# TSOC_CYBLE_R0_0.net
KiCad netlist of a schematic drawn in EAGLE
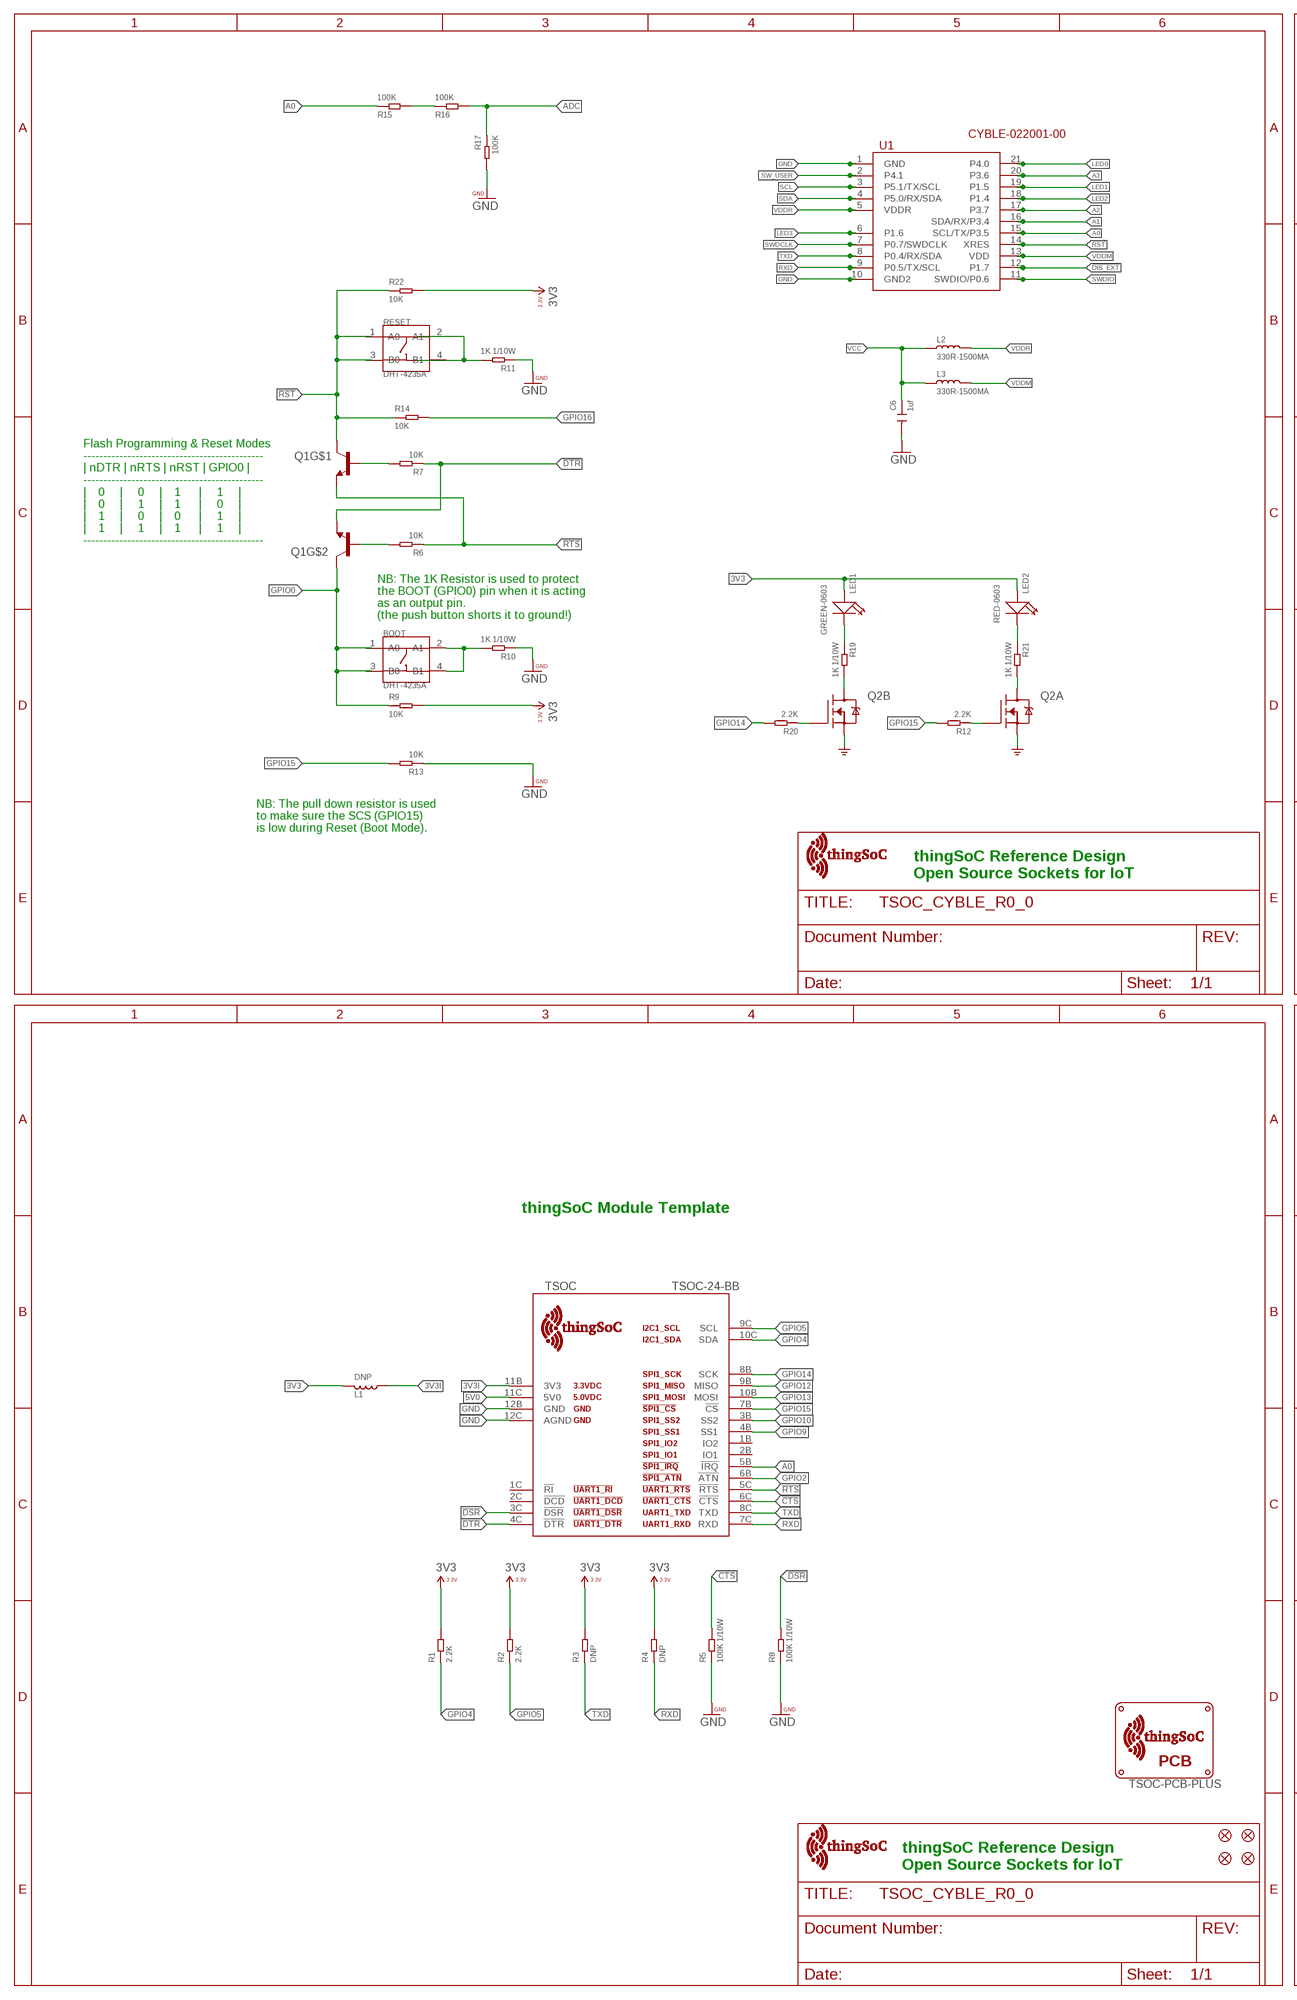
[diagram p0: schematic, sheet 1, part 1 of 2]
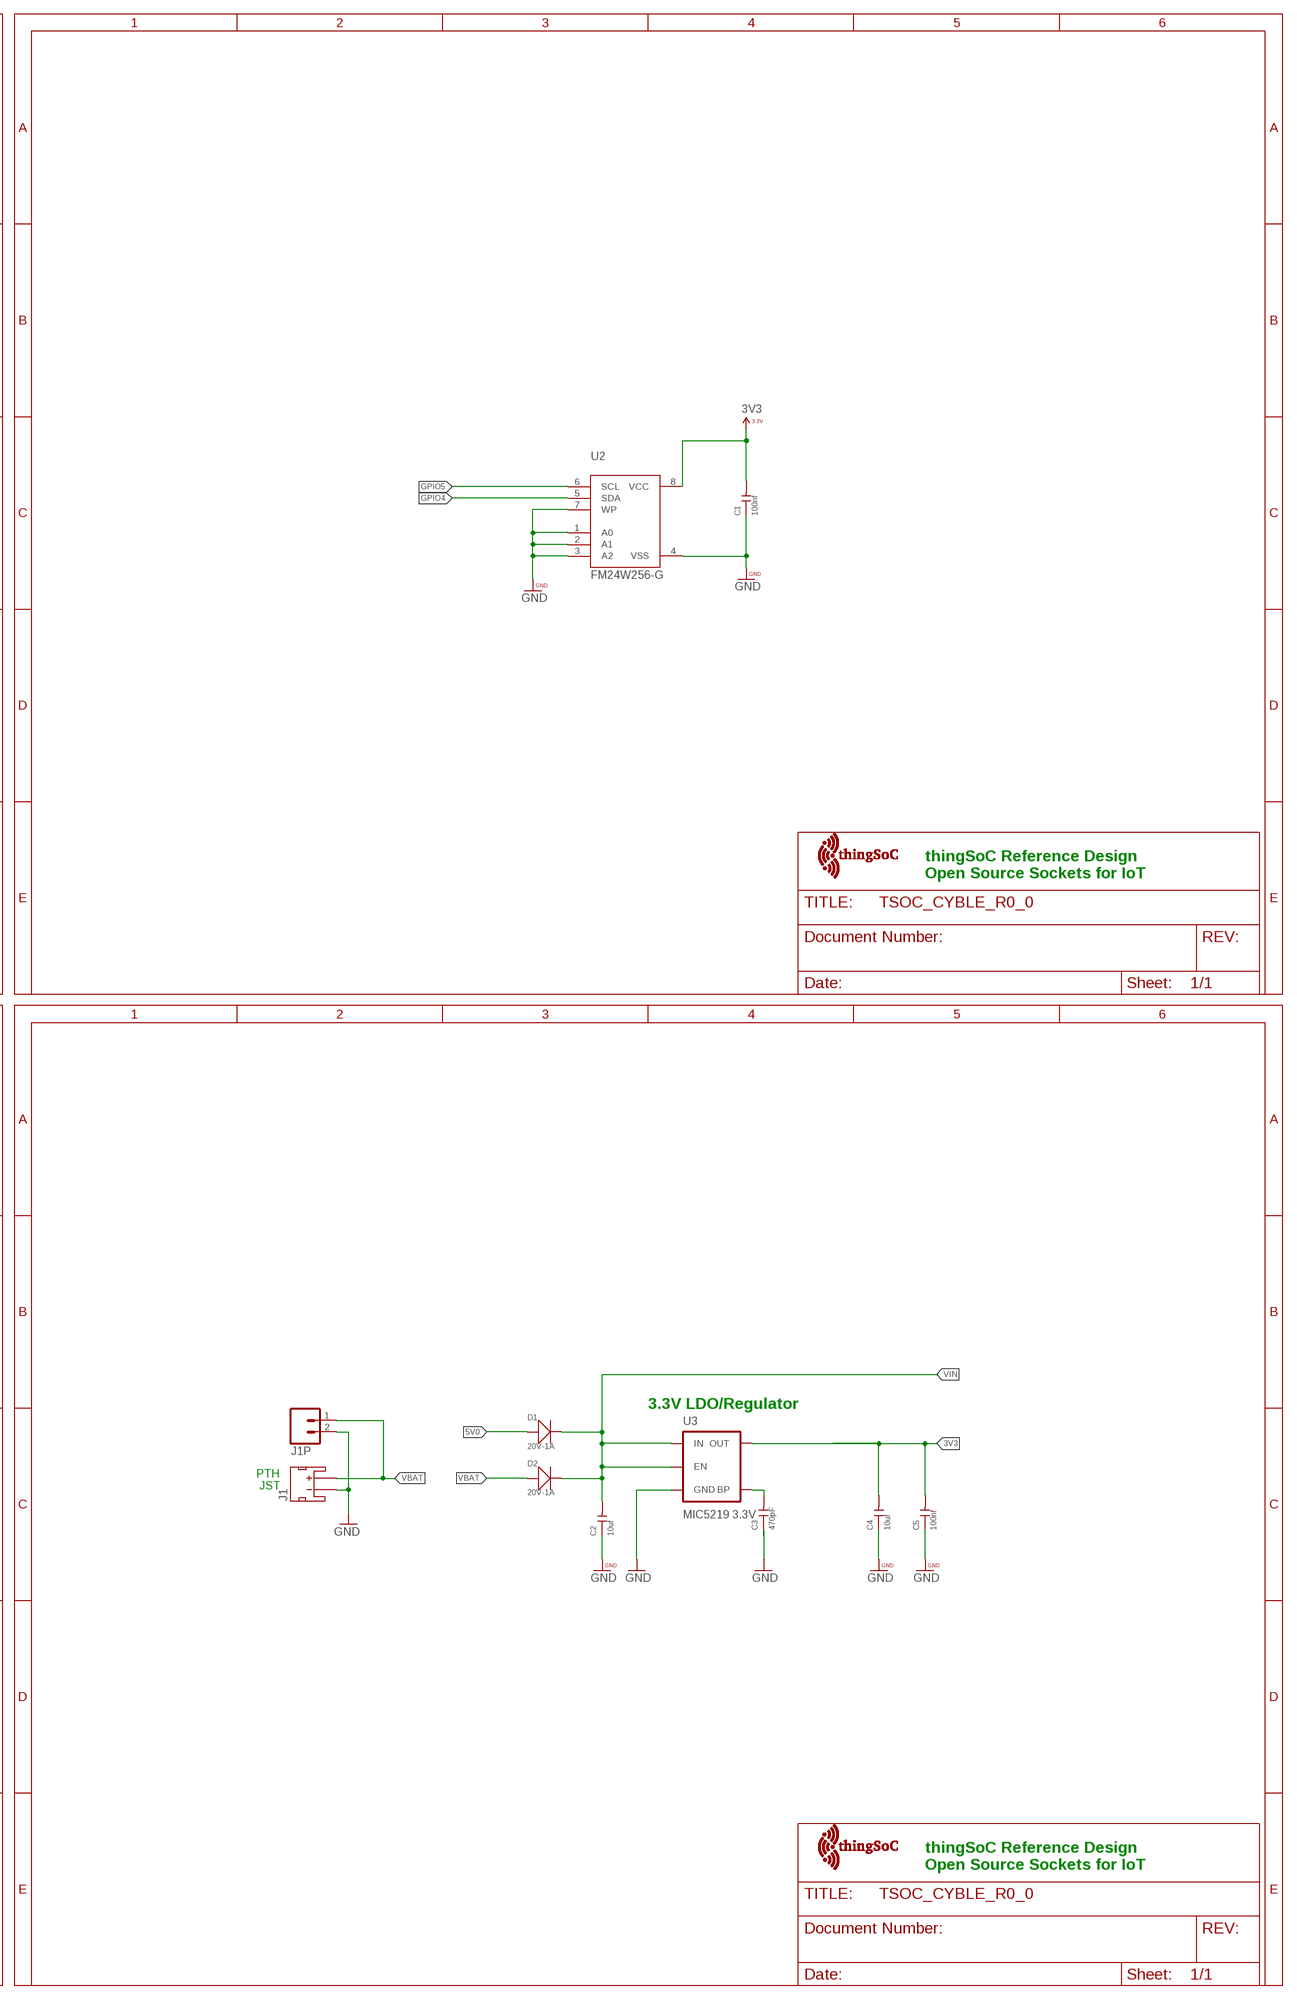
[diagram p1: schematic, sheet 1, part 2 of 2]

(export (version "E")
  (design (tool "Eeschema 10.0.6"))
  (components
    (comp (ref "$$U$1")
      (value "TSOC-LOGO-MED")
      (footprint "eagle-import:TSOC-LOGO-MED")
      (libsource (lib "eagle-import") (part "TSOC-LOGO-MED"))
    )
    (comp (ref "$$U$2")
      (value "TSOC-LOGO-MED")
      (footprint "eagle-import:TSOC-LOGO-MED")
      (libsource (lib "eagle-import") (part "TSOC-LOGO-MED"))
    )
    (comp (ref "BOOT")
      (value "DHT-4235A")
      (footprint "eagle-import:SW4-SMD-4.2X3.2X2.5MM")
      (libsource (lib "eagle-import") (part "SMD-BUTTON-TOP-DHT-4235A(4P-4.2X3.2MM)"))
    )
    (comp (ref "C1")
      (value "100nf")
      (footprint "eagle-import:C0603")
      (fields (field (name "MPN") "CC0603KRX7R9BB104"))
      (libsource (lib "eagle-import") (part "CERAMIC-100NF-50V-10%-X7R(0603)"))
    )
    (comp (ref "C2")
      (value "10uf")
      (footprint "eagle-import:C1206")
      (fields (field (name "MPN") "CC1206KKX5R8BB106"))
      (libsource (lib "eagle-import") (part "CERAMIC-10UF-25V-10%-X5R(1206)"))
    )
    (comp (ref "C3")
      (value "470pF")
      (footprint "eagle-import:C0603")
      (fields (field (name "MPN") "CC0603KRX7R9BB104"))
      (libsource (lib "eagle-import") (part "CERAMIC-100NF-50V-10%-X7R(0603)"))
    )
    (comp (ref "C4")
      (value "10uf")
      (footprint "eagle-import:C1206")
      (fields (field (name "MPN") "CC1206KKX5R8BB106"))
      (libsource (lib "eagle-import") (part "CERAMIC-10UF-25V-10%-X5R(1206)"))
    )
    (comp (ref "C5")
      (value "100nf")
      (footprint "eagle-import:C0603")
      (fields (field (name "MPN") "CC0603KRX7R9BB104"))
      (libsource (lib "eagle-import") (part "CERAMIC-100NF-50V-10%-X7R(0603)"))
    )
    (comp (ref "C6")
      (value "1uf")
      (footprint "eagle-import:C0603")
      (fields (field (name "MPN") "CC0603KRX7R8BB105"))
      (libsource (lib "eagle-import") (part "CERAMIC-1UF-25V-10%-X7R(0603)"))
    )
    (comp (ref "D1")
      (value "20V-1A")
      (footprint "eagle-import:SOD-123")
      (fields (field (name "MPN") "B5819W"))
      (libsource (lib "eagle-import") (part "SMD-DIODE-SCHOTTKY-20V-1A(SOD-123)"))
    )
    (comp (ref "D2")
      (value "20V-1A")
      (footprint "eagle-import:SOD-123")
      (fields (field (name "MPN") "B5819W"))
      (libsource (lib "eagle-import") (part "SMD-DIODE-SCHOTTKY-20V-1A(SOD-123)"))
    )
    (comp (ref "FID1")
      (value "FIDUCIALUFIDUCIAL")
      (footprint "eagle-import:MICRO-FIDUCIAL")
      (libsource (lib "eagle-import") (part "FIDUCIALUFIDUCIAL"))
    )
    (comp (ref "FID2")
      (value "FIDUCIALUFIDUCIAL")
      (footprint "eagle-import:MICRO-FIDUCIAL")
      (libsource (lib "eagle-import") (part "FIDUCIALUFIDUCIAL"))
    )
    (comp (ref "FID3")
      (value "FIDUCIALUFIDUCIAL")
      (footprint "eagle-import:MICRO-FIDUCIAL")
      (libsource (lib "eagle-import") (part "FIDUCIALUFIDUCIAL"))
    )
    (comp (ref "FID4")
      (value "FIDUCIALUFIDUCIAL")
      (footprint "eagle-import:MICRO-FIDUCIAL")
      (libsource (lib "eagle-import") (part "FIDUCIALUFIDUCIAL"))
    )
    (comp (ref "J1")
      (value "JST_2MM_MALE")
      (footprint "eagle-import:JST-2-SMD")
      (libsource (lib "eagle-import") (part "JST_2MM_MALE"))
    )
    (comp (ref "J1P")
      (value "M02-JST-2-PTH-NO_SILK")
      (footprint "eagle-import:JST-2-PTH-NS")
      (libsource (lib "eagle-import") (part "M02-JST-2-PTH-NO_SILK"))
    )
    (comp (ref "L1")
      (value "DNP")
      (footprint "eagle-import:L0603")
      (fields (field (name "MPN") "BLM18AG121SN1D"))
      (libsource (lib "eagle-import") (part "SMD-FERRITE-CHIP-120-OHM-500MA(0603)"))
    )
    (comp (ref "L2")
      (value "330R-1500MA")
      (footprint "eagle-import:L0805")
      (fields (field (name "MPN") "BLM21PG331SN1D"))
      (libsource (lib "eagle-import") (part "SMD-FERRITE-BEAD-330R-1500MA(0805)'0805'"))
    )
    (comp (ref "L3")
      (value "330R-1500MA")
      (footprint "eagle-import:L0805")
      (fields (field (name "MPN") "BLM21PG331SN1D"))
      (libsource (lib "eagle-import") (part "SMD-FERRITE-BEAD-330R-1500MA(0805)'0805'"))
    )
    (comp (ref "LED1")
      (value "GREEN-0603")
      (footprint "eagle-import:LED-0603")
      (fields (field (name "MPN") "19-217-G7C-AN1P2-3T"))
      (libsource (lib "eagle-import") (part "SMD-LED-CLEAR-GREEN(0603)"))
    )
    (comp (ref "LED2")
      (value "RED-0603")
      (footprint "eagle-import:LED-0603")
      (fields (field (name "MPN") "19-217-R6C-AL1M2VY-3T"))
      (libsource (lib "eagle-import") (part "LED-SMD-RED-DIFFUSED(0603)"))
    )
    (comp (ref "PCB")
      (value "TSOC-PCB-PLUS")
      (footprint "eagle-import:TSOC-BB-BRD-PLUS-DIM")
      (libsource (lib "eagle-import") (part "TSOC-PCB-PLUS"))
    )
    (comp (ref "Q1")
      (value "MMBT2222A")
      (footprint "eagle-import:SOT363")
      (libsource (lib "eagle-import") (part "MMDT3904"))
    )
    (comp (ref "Q2")
      (value "FDG1024NZ")
      (footprint "eagle-import:SOT95P280X110-6N")
      (libsource (lib "eagle-import") (part "FDG1024NZ"))
    )
    (comp (ref "R1")
      (value "2.2K")
      (footprint "eagle-import:R0603")
      (fields (field (name "MPN") "RC0603JR-072K2L"))
      (libsource (lib "eagle-import") (part "SMD-RES-2.2K-5%-1/10W(0603)"))
    )
    (comp (ref "R2")
      (value "2.2K")
      (footprint "eagle-import:R0603")
      (fields (field (name "MPN") "RC0603JR-072K2L"))
      (libsource (lib "eagle-import") (part "SMD-RES-2.2K-5%-1/10W(0603)"))
    )
    (comp (ref "R3")
      (value "DNP")
      (footprint "eagle-import:R0603")
      (fields (field (name "MPN") "RC0603JR-072K2L"))
      (libsource (lib "eagle-import") (part "SMD-RES-2.2K-5%-1/10W(0603)"))
    )
    (comp (ref "R4")
      (value "DNP")
      (footprint "eagle-import:R0603")
      (fields (field (name "MPN") "RC0603JR-072K2L"))
      (libsource (lib "eagle-import") (part "SMD-RES-2.2K-5%-1/10W(0603)"))
    )
    (comp (ref "R5")
      (value "100K 1/10W")
      (footprint "eagle-import:R0603")
      (fields (field (name "MPN") "RC0603JR-07100KL"))
      (libsource (lib "eagle-import") (part "SMD-RES-100K-5%-1/10W(0603)"))
    )
    (comp (ref "R6")
      (value "10K")
      (footprint "eagle-import:R0603")
      (fields (field (name "MPN") "RC0603FR-0710KL"))
      (libsource (lib "eagle-import") (part "SMD-RES-10K-1%-1/10W(0603)"))
    )
    (comp (ref "R7")
      (value "10K")
      (footprint "eagle-import:R0603")
      (fields (field (name "MPN") "RC0603FR-0710KL"))
      (libsource (lib "eagle-import") (part "SMD-RES-10K-1%-1/10W(0603)"))
    )
    (comp (ref "R8")
      (value "100K 1/10W")
      (footprint "eagle-import:R0603")
      (fields (field (name "MPN") "RC0603JR-07100KL"))
      (libsource (lib "eagle-import") (part "SMD-RES-100K-5%-1/10W(0603)"))
    )
    (comp (ref "R9")
      (value "10K")
      (footprint "eagle-import:R0603")
      (fields (field (name "MPN") "RC0603FR-0710KL"))
      (libsource (lib "eagle-import") (part "SMD-RES-10K-1%-1/10W(0603)"))
    )
    (comp (ref "R10")
      (value "1K 1/10W")
      (footprint "eagle-import:R0603")
      (fields (field (name "MPN") "RC0603JR-071KL"))
      (libsource (lib "eagle-import") (part "SMD-RES-1K-5%-1/10W(0603)"))
    )
    (comp (ref "R11")
      (value "1K 1/10W")
      (footprint "eagle-import:R0603")
      (fields (field (name "MPN") "RC0603JR-071KL"))
      (libsource (lib "eagle-import") (part "SMD-RES-1K-5%-1/10W(0603)"))
    )
    (comp (ref "R12")
      (value "2.2K")
      (footprint "eagle-import:R0603")
      (fields (field (name "MPN") "RC0603JR-072K2L"))
      (libsource (lib "eagle-import") (part "SMD-RES-2.2K-5%-1/10W(0603)"))
    )
    (comp (ref "R13")
      (value "10K")
      (footprint "eagle-import:R0603")
      (fields (field (name "MPN") "RC0603FR-0710KL"))
      (libsource (lib "eagle-import") (part "SMD-RES-10K-1%-1/10W(0603)"))
    )
    (comp (ref "R14")
      (value "10K")
      (footprint "eagle-import:R0603")
      (fields (field (name "MPN") "RC0603FR-0710KL"))
      (libsource (lib "eagle-import") (part "SMD-RES-10K-1%-1/10W(0603)"))
    )
    (comp (ref "R15")
      (value "100K")
      (footprint "eagle-import:R0603")
      (fields (field (name "MPN") "RC0603FR-07100KL"))
      (libsource (lib "eagle-import") (part "SMD-RES-100K-1%-1/10W(0603)"))
    )
    (comp (ref "R16")
      (value "100K")
      (footprint "eagle-import:R0603")
      (fields (field (name "MPN") "RC0603FR-07100KL"))
      (libsource (lib "eagle-import") (part "SMD-RES-100K-1%-1/10W(0603)"))
    )
    (comp (ref "R17")
      (value "100K")
      (footprint "eagle-import:R0603")
      (fields (field (name "MPN") "RC0603FR-07100KL"))
      (libsource (lib "eagle-import") (part "SMD-RES-100K-1%-1/10W(0603)"))
    )
    (comp (ref "R19")
      (value "1K 1/10W")
      (footprint "eagle-import:R0603")
      (fields (field (name "MPN") "RC0603JR-071KL"))
      (libsource (lib "eagle-import") (part "SMD-RES-1K-5%-1/10W(0603)"))
    )
    (comp (ref "R20")
      (value "2.2K")
      (footprint "eagle-import:R0603")
      (fields (field (name "MPN") "RC0603JR-072K2L"))
      (libsource (lib "eagle-import") (part "SMD-RES-2.2K-5%-1/10W(0603)"))
    )
    (comp (ref "R21")
      (value "1K 1/10W")
      (footprint "eagle-import:R0603")
      (fields (field (name "MPN") "RC0603JR-071KL"))
      (libsource (lib "eagle-import") (part "SMD-RES-1K-5%-1/10W(0603)"))
    )
    (comp (ref "R22")
      (value "10K")
      (footprint "eagle-import:R0603")
      (fields (field (name "MPN") "RC0603FR-0710KL"))
      (libsource (lib "eagle-import") (part "SMD-RES-10K-1%-1/10W(0603)"))
    )
    (comp (ref "RESET")
      (value "DHT-4235A")
      (footprint "eagle-import:SW4-SMD-4.2X3.2X2.5MM")
      (libsource (lib "eagle-import") (part "SMD-BUTTON-TOP-DHT-4235A(4P-4.2X3.2MM)"))
    )
    (comp (ref "TSOC")
      (value "TSOC-24-BB")
      (footprint "eagle-import:TSOC-BB-S24")
      (libsource (lib "eagle-import") (part "TSOC-24-BB"))
    )
    (comp (ref "U$101")
      (value "TSOC-LOGO-MED")
      (footprint "eagle-import:TSOC-LOGO-MED")
      (libsource (lib "eagle-import") (part "TSOC-LOGO-MED"))
    )
    (comp (ref "U$102")
      (value "TSOC-LOGO-MED")
      (footprint "eagle-import:TSOC-LOGO-MED")
      (libsource (lib "eagle-import") (part "TSOC-LOGO-MED"))
    )
    (comp (ref "U1")
      (value "CYBLE-022001-00")
      (footprint "eagle-import:PROC-BLE-10MM-21")
      (libsource (lib "eagle-import") (part "CYBLE-022001-00"))
    )
    (comp (ref "U2")
      (value "FM24W256-G")
      (footprint "eagle-import:SO08")
      (libsource (lib "eagle-import") (part "FM24W256-G"))
    )
    (comp (ref "U3")
      (value "MIC5219 3.3V")
      (footprint "eagle-import:SOT23-5")
      (libsource (lib "eagle-import") (part "V_REG_MIC52193.3V"))
    )
  )
  (nets
    (net (code "1") (name "/~{CTS}") (class "Default")
      (node (ref "R5") (pin "2") (pinfunction "2_2") (pintype "passive"))
      (node (ref "TSOC") (pin "6C") (pinfunction "~{CTS}_6C") (pintype "bidirectional"))
    )
    (net (code "2") (name "/~{DIS_EXT}") (class "Default")
      (node (ref "U1") (pin "12") (pinfunction "P1.7_12") (pintype "bidirectional"))
    )
    (net (code "3") (name "/~{DSR}") (class "Default")
      (node (ref "R8") (pin "2") (pinfunction "2_2") (pintype "passive"))
      (node (ref "TSOC") (pin "3C") (pinfunction "~{DSR}_3C") (pintype "bidirectional"))
    )
    (net (code "4") (name "/~{DTR}") (class "Default")
      (node (ref "Q1") (pin "1") (pinfunction "E_1") (pintype "passive"))
      (node (ref "R7") (pin "1") (pinfunction "1_1") (pintype "passive"))
      (node (ref "TSOC") (pin "4C") (pinfunction "~{DTR}_4C") (pintype "bidirectional"))
    )
    (net (code "5") (name "/~{RST}") (class "Default")
      (node (ref "Q1") (pin "3") (pinfunction "C_3") (pintype "passive"))
      (node (ref "R14") (pin "1") (pinfunction "1_1") (pintype "passive"))
      (node (ref "R22") (pin "1") (pinfunction "1_1") (pintype "passive"))
      (node (ref "RESET") (pin "1") (pinfunction "A0_1") (pintype "bidirectional"))
      (node (ref "RESET") (pin "3") (pinfunction "B0_3") (pintype "bidirectional"))
      (node (ref "U1") (pin "14") (pinfunction "XRES_14") (pintype "input"))
    )
    (net (code "6") (name "/~{RTS}") (class "Default")
      (node (ref "Q1") (pin "4") (pinfunction "E_4") (pintype "passive"))
      (node (ref "R6") (pin "1") (pinfunction "1_1") (pintype "passive"))
      (node (ref "TSOC") (pin "5C") (pinfunction "~{RTS}_5C") (pintype "bidirectional"))
    )
    (net (code "7") (name "3V3") (class "Default")
      (node (ref "C1") (pin "2") (pinfunction "2_2") (pintype "passive"))
      (node (ref "C4") (pin "2") (pinfunction "2_2") (pintype "passive"))
      (node (ref "C5") (pin "2") (pinfunction "2_2") (pintype "passive"))
      (node (ref "L1") (pin "1") (pinfunction "1_1") (pintype "passive"))
      (node (ref "LED1") (pin "+") (pinfunction "+_+") (pintype "passive"))
      (node (ref "LED2") (pin "+") (pinfunction "+_+") (pintype "passive"))
      (node (ref "R1") (pin "2") (pinfunction "2_2") (pintype "passive"))
      (node (ref "R2") (pin "2") (pinfunction "2_2") (pintype "passive"))
      (node (ref "R22") (pin "2") (pinfunction "2_2") (pintype "passive"))
      (node (ref "R3") (pin "2") (pinfunction "2_2") (pintype "passive"))
      (node (ref "R4") (pin "2") (pinfunction "2_2") (pintype "passive"))
      (node (ref "R9") (pin "2") (pinfunction "2_2") (pintype "passive"))
      (node (ref "U2") (pin "8") (pinfunction "VCC_8") (pintype "power_in"))
      (node (ref "U3") (pin "5") (pinfunction "OUT_5") (pintype "passive"))
    )
    (net (code "8") (name "3V3I") (class "Default")
      (node (ref "L1") (pin "2") (pinfunction "2_2") (pintype "passive"))
      (node (ref "TSOC") (pin "11B") (pinfunction "3V3_11B") (pintype "bidirectional"))
    )
    (net (code "9") (name "5V0") (class "Default")
      (node (ref "D1") (pin "+") (pinfunction "+_+") (pintype "passive"))
      (node (ref "TSOC") (pin "11C") (pinfunction "5V0_11C") (pintype "bidirectional"))
    )
    (net (code "10") (name "A0") (class "Default")
      (node (ref "R15") (pin "1") (pinfunction "1_1") (pintype "passive"))
      (node (ref "TSOC") (pin "5B") (pinfunction "~{IRQ}_5B") (pintype "bidirectional"))
      (node (ref "U1") (pin "15") (pinfunction "SCL/TX/P3.5_15") (pintype "bidirectional"))
    )
    (net (code "11") (name "A1") (class "Default")
      (node (ref "U1") (pin "16") (pinfunction "SDA/RX/P3.4_16") (pintype "bidirectional"))
    )
    (net (code "12") (name "A2") (class "Default")
      (node (ref "U1") (pin "17") (pinfunction "P3.7_17") (pintype "bidirectional"))
    )
    (net (code "13") (name "A3") (class "Default")
      (node (ref "U1") (pin "20") (pinfunction "P3.6_20") (pintype "bidirectional"))
    )
    (net (code "14") (name "ADC") (class "Default")
      (node (ref "R16") (pin "2") (pinfunction "2_2") (pintype "passive"))
      (node (ref "R17") (pin "1") (pinfunction "1_1") (pintype "passive"))
    )
    (net (code "15") (name "GND") (class "Default")
      (node (ref "C1") (pin "1") (pinfunction "1_1") (pintype "passive"))
      (node (ref "C2") (pin "1") (pinfunction "1_1") (pintype "passive"))
      (node (ref "C3") (pin "1") (pinfunction "1_1") (pintype "passive"))
      (node (ref "C4") (pin "1") (pinfunction "1_1") (pintype "passive"))
      (node (ref "C5") (pin "1") (pinfunction "1_1") (pintype "passive"))
      (node (ref "C6") (pin "2") (pinfunction "2_2") (pintype "passive"))
      (node (ref "J1") (pin "1") (pinfunction "-_1") (pintype "bidirectional"))
      (node (ref "J1P") (pin "2") (pinfunction "2_2") (pintype "passive"))
      (node (ref "Q2") (pin "1") (pinfunction "S_1") (pintype "passive"))
      (node (ref "Q2") (pin "4") (pinfunction "S_4") (pintype "passive"))
      (node (ref "R10") (pin "1") (pinfunction "1_1") (pintype "passive"))
      (node (ref "R11") (pin "1") (pinfunction "1_1") (pintype "passive"))
      (node (ref "R13") (pin "1") (pinfunction "1_1") (pintype "passive"))
      (node (ref "R17") (pin "2") (pinfunction "2_2") (pintype "passive"))
      (node (ref "R5") (pin "1") (pinfunction "1_1") (pintype "passive"))
      (node (ref "R8") (pin "1") (pinfunction "1_1") (pintype "passive"))
      (node (ref "TSOC") (pin "12B") (pinfunction "GND_12B") (pintype "bidirectional"))
      (node (ref "TSOC") (pin "12C") (pinfunction "AGND_12C") (pintype "bidirectional"))
      (node (ref "U1") (pin "1") (pinfunction "GND_1") (pintype "power_in"))
      (node (ref "U1") (pin "10") (pinfunction "GND2_10") (pintype "power_in"))
      (node (ref "U2") (pin "1") (pinfunction "A0_1") (pintype "bidirectional"))
      (node (ref "U2") (pin "2") (pinfunction "A1_2") (pintype "bidirectional"))
      (node (ref "U2") (pin "3") (pinfunction "A2_3") (pintype "bidirectional"))
      (node (ref "U2") (pin "4") (pinfunction "VSS_4") (pintype "power_in"))
      (node (ref "U2") (pin "7") (pinfunction "WP_7") (pintype "bidirectional"))
      (node (ref "U3") (pin "2") (pinfunction "GND_2") (pintype "input"))
    )
    (net (code "16") (name "GPIO0") (class "Default")
      (node (ref "BOOT") (pin "1") (pinfunction "A0_1") (pintype "bidirectional"))
      (node (ref "BOOT") (pin "3") (pinfunction "B0_3") (pintype "bidirectional"))
      (node (ref "Q1") (pin "6") (pinfunction "C_6") (pintype "passive"))
      (node (ref "R9") (pin "1") (pinfunction "1_1") (pintype "passive"))
    )
    (net (code "17") (name "GPIO2") (class "Default")
      (node (ref "TSOC") (pin "6B") (pinfunction "~{ATN}_6B") (pintype "bidirectional"))
    )
    (net (code "18") (name "GPIO4") (class "Default")
      (node (ref "R1") (pin "1") (pinfunction "1_1") (pintype "passive"))
      (node (ref "TSOC") (pin "10C") (pinfunction "SDA_10C") (pintype "bidirectional"))
      (node (ref "U2") (pin "5") (pinfunction "SDA_5") (pintype "bidirectional"))
    )
    (net (code "19") (name "GPIO5") (class "Default")
      (node (ref "R2") (pin "1") (pinfunction "1_1") (pintype "passive"))
      (node (ref "TSOC") (pin "9C") (pinfunction "SCL_9C") (pintype "bidirectional"))
      (node (ref "U2") (pin "6") (pinfunction "SCL_6") (pintype "bidirectional"))
    )
    (net (code "20") (name "GPIO9") (class "Default")
      (node (ref "TSOC") (pin "4B") (pinfunction "SS1_4B") (pintype "bidirectional"))
    )
    (net (code "21") (name "GPIO10") (class "Default")
      (node (ref "TSOC") (pin "3B") (pinfunction "SS2_3B") (pintype "bidirectional"))
    )
    (net (code "22") (name "GPIO12") (class "Default")
      (node (ref "TSOC") (pin "9B") (pinfunction "MISO_9B") (pintype "bidirectional"))
    )
    (net (code "23") (name "GPIO13") (class "Default")
      (node (ref "TSOC") (pin "10B") (pinfunction "MOSI_10B") (pintype "bidirectional"))
    )
    (net (code "24") (name "GPIO14") (class "Default")
      (node (ref "R20") (pin "2") (pinfunction "2_2") (pintype "passive"))
      (node (ref "TSOC") (pin "8B") (pinfunction "SCK_8B") (pintype "bidirectional"))
    )
    (net (code "25") (name "GPIO15") (class "Default")
      (node (ref "R12") (pin "2") (pinfunction "2_2") (pintype "passive"))
      (node (ref "R13") (pin "2") (pinfunction "2_2") (pintype "passive"))
      (node (ref "TSOC") (pin "7B") (pinfunction "~{CS}_7B") (pintype "bidirectional"))
    )
    (net (code "26") (name "GPIO16") (class "Default")
      (node (ref "R14") (pin "2") (pinfunction "2_2") (pintype "passive"))
    )
    (net (code "27") (name "LED0") (class "Default")
      (node (ref "U1") (pin "21") (pinfunction "P4.0_21") (pintype "bidirectional"))
    )
    (net (code "28") (name "LED1") (class "Default")
      (node (ref "LED1") (pin "-") (pinfunction "-_-") (pintype "passive"))
      (node (ref "R19") (pin "1") (pinfunction "1_1") (pintype "passive"))
      (node (ref "U1") (pin "19") (pinfunction "P1.5_19") (pintype "bidirectional"))
    )
    (net (code "29") (name "LED2") (class "Default")
      (node (ref "LED2") (pin "-") (pinfunction "-_-") (pintype "passive"))
      (node (ref "R21") (pin "1") (pinfunction "1_1") (pintype "passive"))
      (node (ref "U1") (pin "18") (pinfunction "P1.4_18") (pintype "bidirectional"))
    )
    (net (code "30") (name "LED3") (class "Default")
      (node (ref "U1") (pin "6") (pinfunction "P1.6_6") (pintype "bidirectional"))
    )
    (net (code "31") (name "Net-(BOOT-A1)") (class "Default")
      (node (ref "BOOT") (pin "2") (pinfunction "A1_2") (pintype "bidirectional"))
      (node (ref "BOOT") (pin "4") (pinfunction "B1_4") (pintype "bidirectional"))
      (node (ref "R10") (pin "2") (pinfunction "2_2") (pintype "passive"))
    )
    (net (code "32") (name "Net-(Q1A-B)") (class "Default")
      (node (ref "Q1") (pin "5") (pinfunction "B_5") (pintype "passive"))
      (node (ref "R7") (pin "2") (pinfunction "2_2") (pintype "passive"))
    )
    (net (code "33") (name "Net-(Q1B-B)") (class "Default")
      (node (ref "Q1") (pin "2") (pinfunction "B_2") (pintype "passive"))
      (node (ref "R6") (pin "2") (pinfunction "2_2") (pintype "passive"))
    )
    (net (code "34") (name "Net-(Q2A-D)") (class "Default")
      (node (ref "Q2") (pin "6") (pinfunction "D_6") (pintype "passive"))
      (node (ref "R21") (pin "2") (pinfunction "2_2") (pintype "passive"))
    )
    (net (code "35") (name "Net-(Q2A-G)") (class "Default")
      (node (ref "Q2") (pin "2") (pinfunction "G_2") (pintype "passive"))
      (node (ref "R12") (pin "1") (pinfunction "1_1") (pintype "passive"))
    )
    (net (code "36") (name "Net-(Q2B-D)") (class "Default")
      (node (ref "Q2") (pin "3") (pinfunction "D_3") (pintype "passive"))
      (node (ref "R19") (pin "2") (pinfunction "2_2") (pintype "passive"))
    )
    (net (code "37") (name "Net-(Q2B-G)") (class "Default")
      (node (ref "Q2") (pin "5") (pinfunction "G_5") (pintype "passive"))
      (node (ref "R20") (pin "1") (pinfunction "1_1") (pintype "passive"))
    )
    (net (code "38") (name "Net-(R15-Pad2)") (class "Default")
      (node (ref "R15") (pin "2") (pinfunction "2_2") (pintype "passive"))
      (node (ref "R16") (pin "1") (pinfunction "1_1") (pintype "passive"))
    )
    (net (code "39") (name "Net-(RESET-A1)") (class "Default")
      (node (ref "R11") (pin "2") (pinfunction "2_2") (pintype "passive"))
      (node (ref "RESET") (pin "2") (pinfunction "A1_2") (pintype "bidirectional"))
      (node (ref "RESET") (pin "4") (pinfunction "B1_4") (pintype "bidirectional"))
    )
    (net (code "40") (name "Net-(U3-BP)") (class "Default")
      (node (ref "C3") (pin "2") (pinfunction "2_2") (pintype "passive"))
      (node (ref "U3") (pin "4") (pinfunction "BP_4") (pintype "input"))
    )
    (net (code "41") (name "RXD") (class "Default")
      (node (ref "R4") (pin "1") (pinfunction "1_1") (pintype "passive"))
      (node (ref "TSOC") (pin "7C") (pinfunction "RXD_7C") (pintype "bidirectional"))
      (node (ref "U1") (pin "9") (pinfunction "P0.5/TX/SCL_9") (pintype "bidirectional"))
    )
    (net (code "42") (name "SCL") (class "Default")
      (node (ref "U1") (pin "3") (pinfunction "P5.1/TX/SCL_3") (pintype "bidirectional"))
    )
    (net (code "43") (name "SDA") (class "Default")
      (node (ref "U1") (pin "4") (pinfunction "P5.0/RX/SDA_4") (pintype "bidirectional"))
    )
    (net (code "44") (name "SWDCLK") (class "Default")
      (node (ref "U1") (pin "7") (pinfunction "P0.7/SWDCLK_7") (pintype "bidirectional"))
    )
    (net (code "45") (name "SWDIO") (class "Default")
      (node (ref "U1") (pin "11") (pinfunction "SWDIO/P0.6_11") (pintype "bidirectional"))
    )
    (net (code "46") (name "SW_USER") (class "Default")
      (node (ref "U1") (pin "2") (pinfunction "P4.1_2") (pintype "bidirectional"))
    )
    (net (code "47") (name "TXD") (class "Default")
      (node (ref "R3") (pin "1") (pinfunction "1_1") (pintype "passive"))
      (node (ref "TSOC") (pin "8C") (pinfunction "TXD_8C") (pintype "bidirectional"))
      (node (ref "U1") (pin "8") (pinfunction "P0.4/RX/SDA_8") (pintype "bidirectional"))
    )
    (net (code "48") (name "VBAT") (class "Default")
      (node (ref "D2") (pin "+") (pinfunction "+_+") (pintype "passive"))
      (node (ref "J1") (pin "2") (pinfunction "+_2") (pintype "bidirectional"))
      (node (ref "J1P") (pin "1") (pinfunction "1_1") (pintype "passive"))
    )
    (net (code "49") (name "VCC") (class "Default")
      (node (ref "C6") (pin "1") (pinfunction "1_1") (pintype "passive"))
      (node (ref "L2") (pin "1") (pinfunction "1_1") (pintype "passive"))
      (node (ref "L3") (pin "1") (pinfunction "1_1") (pintype "passive"))
    )
    (net (code "50") (name "VDDM") (class "Default")
      (node (ref "L3") (pin "2") (pinfunction "2_2") (pintype "passive"))
      (node (ref "U1") (pin "13") (pinfunction "VDD_13") (pintype "power_in"))
    )
    (net (code "51") (name "VDDR") (class "Default")
      (node (ref "L2") (pin "2") (pinfunction "2_2") (pintype "passive"))
      (node (ref "U1") (pin "5") (pinfunction "VDDR_5") (pintype "power_in"))
    )
    (net (code "52") (name "VIN") (class "Default")
      (node (ref "C2") (pin "2") (pinfunction "2_2") (pintype "passive"))
      (node (ref "D1") (pin "-") (pinfunction "-_-") (pintype "passive"))
      (node (ref "D2") (pin "-") (pinfunction "-_-") (pintype "passive"))
      (node (ref "U3") (pin "1") (pinfunction "IN_1") (pintype "input"))
      (node (ref "U3") (pin "3") (pinfunction "EN_3") (pintype "input"))
    )
    (net (code "53") (name "unconnected-(J1-PAD1-PadNC1)") (class "Default")
      (node (ref "J1") (pin "NC1") (pinfunction "PAD1_NC1") (pintype "bidirectional"))
    )
    (net (code "54") (name "unconnected-(J1-PAD2-PadNC2)") (class "Default")
      (node (ref "J1") (pin "NC2") (pinfunction "PAD2_NC2") (pintype "bidirectional"))
    )
    (net (code "55") (name "unconnected-(TSOC-IO1-Pad2B)") (class "Default")
      (node (ref "TSOC") (pin "2B") (pinfunction "IO1_2B") (pintype "bidirectional"))
    )
    (net (code "56") (name "unconnected-(TSOC-IO2-Pad1B)") (class "Default")
      (node (ref "TSOC") (pin "1B") (pinfunction "IO2_1B") (pintype "bidirectional"))
    )
    (net (code "57") (name "unconnected-(TSOC-~{DCD}-Pad2C)") (class "Default")
      (node (ref "TSOC") (pin "2C") (pinfunction "~{DCD}_2C") (pintype "bidirectional"))
    )
    (net (code "58") (name "unconnected-(TSOC-~{RI}-Pad1C)") (class "Default")
      (node (ref "TSOC") (pin "1C") (pinfunction "~{RI}_1C") (pintype "bidirectional"))
    )
  )
)
